# hiiri627v071_ssop.net
KiCad netlist of a schematic drawn in Altium Designer
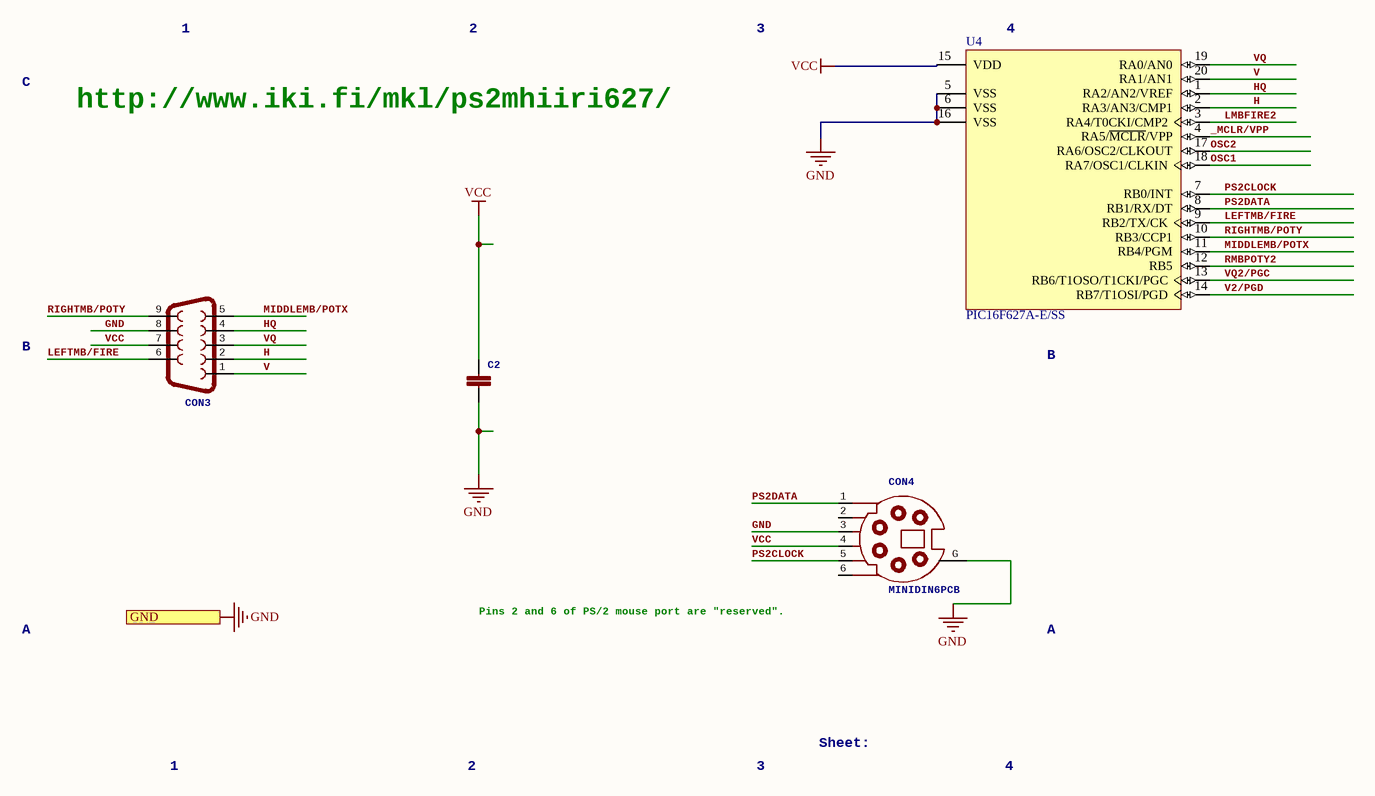
[diagram p0: hiiri627v071_ssop.SchDoc]

(export (version "E")
  (design (tool "Eeschema 10.0.6"))
  (components
    (comp (ref "C2")
      (value "C-EUC0805K")
      (footprint "C0805K")
      (description "CAPACITOR, European symbol")
      (libsource (lib "rcl") (part "C-EUC0805K"))
    )
    (comp (ref "CON3")
      (value "F09D")
      (footprint "F09D")
      (description "SUB-D")
      (fields (field (name "LIBRARYNAME") "con-subd"))
      (libsource (lib "con-subd") (part "F09D"))
    )
    (comp (ref "CON4")
      (value "MINIDIN6PCB")
      (footprint "MINIDIN6PCB")
      (fields (field (name "LIBRARYNAME") "0mikacon"))
      (libsource (lib "0mikacon") (part "MINIDIN6PCB"))
    )
    (comp (ref "U4")
      (value "PIC16F627A-E/SS")
      (footprint "SSOP-SS20_N")
      (fields (field (name "PUBLISHER") "Altium Limited"))
      (libsource (lib "Microchip Microcontroller 8-Bit PIC16") (part "PIC16F627A-E/SS"))
    )
  )
  (nets
    (net (code "1") (name "/H") (class "Default")
      (node (ref "CON3") (pin "2") (pinfunction "2_2") (pintype "passive"))
      (node (ref "U4") (pin "2") (pinfunction "RA3/AN3/CMP1_2") (pintype "bidirectional"))
    )
    (net (code "2") (name "/HQ") (class "Default")
      (node (ref "CON3") (pin "4") (pinfunction "4_4") (pintype "passive"))
      (node (ref "U4") (pin "1") (pinfunction "RA2/AN2/VREF_1") (pintype "bidirectional"))
    )
    (net (code "3") (name "/LEFTMB{slash}FIRE") (class "Default")
      (node (ref "CON3") (pin "6") (pinfunction "6_6") (pintype "passive"))
      (node (ref "U4") (pin "9") (pinfunction "RB2/TX/CK_9") (pintype "bidirectional"))
    )
    (net (code "4") (name "/LMBFIRE2") (class "Default")
      (node (ref "U4") (pin "3") (pinfunction "RA4/T0CKI/CMP2_3") (pintype "bidirectional"))
    )
    (net (code "5") (name "/MIDDLEMB{slash}POTX") (class "Default")
      (node (ref "CON3") (pin "5") (pinfunction "5_5") (pintype "passive"))
      (node (ref "U4") (pin "11") (pinfunction "RB4/PGM_11") (pintype "bidirectional"))
    )
    (net (code "6") (name "/OSC1") (class "Default")
      (node (ref "U4") (pin "18") (pinfunction "RA7/OSC1/CLKIN_18") (pintype "bidirectional"))
    )
    (net (code "7") (name "/OSC2") (class "Default")
      (node (ref "U4") (pin "17") (pinfunction "RA6/OSC2/CLKOUT_17") (pintype "bidirectional"))
    )
    (net (code "8") (name "/PS2CLOCK") (class "Default")
      (node (ref "CON4") (pin "5") (pinfunction "5_5") (pintype "passive"))
      (node (ref "U4") (pin "7") (pinfunction "RB0/INT_7") (pintype "bidirectional"))
    )
    (net (code "9") (name "/PS2DATA") (class "Default")
      (node (ref "CON4") (pin "1") (pinfunction "1_1") (pintype "passive"))
      (node (ref "U4") (pin "8") (pinfunction "RB1/RX/DT_8") (pintype "bidirectional"))
    )
    (net (code "10") (name "/RIGHTMB{slash}POTY") (class "Default")
      (node (ref "CON3") (pin "9") (pinfunction "9_9") (pintype "passive"))
      (node (ref "U4") (pin "10") (pinfunction "RB3/CCP1_10") (pintype "bidirectional"))
    )
    (net (code "11") (name "/RMBPOTY2") (class "Default")
      (node (ref "U4") (pin "12") (pinfunction "RB5_12") (pintype "bidirectional"))
    )
    (net (code "12") (name "/V") (class "Default")
      (node (ref "CON3") (pin "1") (pinfunction "1_1") (pintype "passive"))
      (node (ref "U4") (pin "20") (pinfunction "RA1/AN1_20") (pintype "bidirectional"))
    )
    (net (code "13") (name "/V2{slash}PGD") (class "Default")
      (node (ref "U4") (pin "14") (pinfunction "RB7/T1OSI/PGD_14") (pintype "bidirectional"))
    )
    (net (code "14") (name "/VQ") (class "Default")
      (node (ref "CON3") (pin "3") (pinfunction "3_3") (pintype "passive"))
      (node (ref "U4") (pin "19") (pinfunction "RA0/AN0_19") (pintype "bidirectional"))
    )
    (net (code "15") (name "/VQ2{slash}PGC") (class "Default")
      (node (ref "U4") (pin "13") (pinfunction "RB6/T1OSO/T1CKI/PGC_13") (pintype "bidirectional"))
    )
    (net (code "16") (name "/_MCLR{slash}VPP") (class "Default")
      (node (ref "U4") (pin "4") (pinfunction "RA5/~{MCLR}/VPP_4") (pintype "bidirectional"))
    )
    (net (code "17") (name "GND") (class "Default")
      (node (ref "C2") (pin "2") (pinfunction "2_2") (pintype "passive"))
      (node (ref "CON3") (pin "8") (pinfunction "8_8") (pintype "passive"))
      (node (ref "CON4") (pin "3") (pinfunction "3_3") (pintype "passive"))
      (node (ref "CON4") (pin "G") (pinfunction "G_G") (pintype "passive"))
      (node (ref "U4") (pin "16") (pinfunction "VSS_16") (pintype "power_in"))
      (node (ref "U4") (pin "5") (pinfunction "VSS_5") (pintype "power_in"))
      (node (ref "U4") (pin "6") (pinfunction "VSS_6") (pintype "power_in"))
    )
    (net (code "18") (name "VCC") (class "Default")
      (node (ref "C2") (pin "1") (pinfunction "1_1") (pintype "passive"))
      (node (ref "CON3") (pin "7") (pinfunction "7_7") (pintype "passive"))
      (node (ref "CON4") (pin "4") (pinfunction "4_4") (pintype "passive"))
      (node (ref "U4") (pin "15") (pinfunction "VDD_15") (pintype "power_in"))
    )
    (net (code "19") (name "unconnected-(CON4-Pad2)") (class "Default")
      (node (ref "CON4") (pin "2") (pinfunction "2_2") (pintype "passive"))
    )
    (net (code "20") (name "unconnected-(CON4-Pad6)") (class "Default")
      (node (ref "CON4") (pin "6") (pinfunction "6_6") (pintype "passive"))
    )
  )
)
